# qtpy_midibff.net
KiCad netlist of a schematic drawn in EAGLE
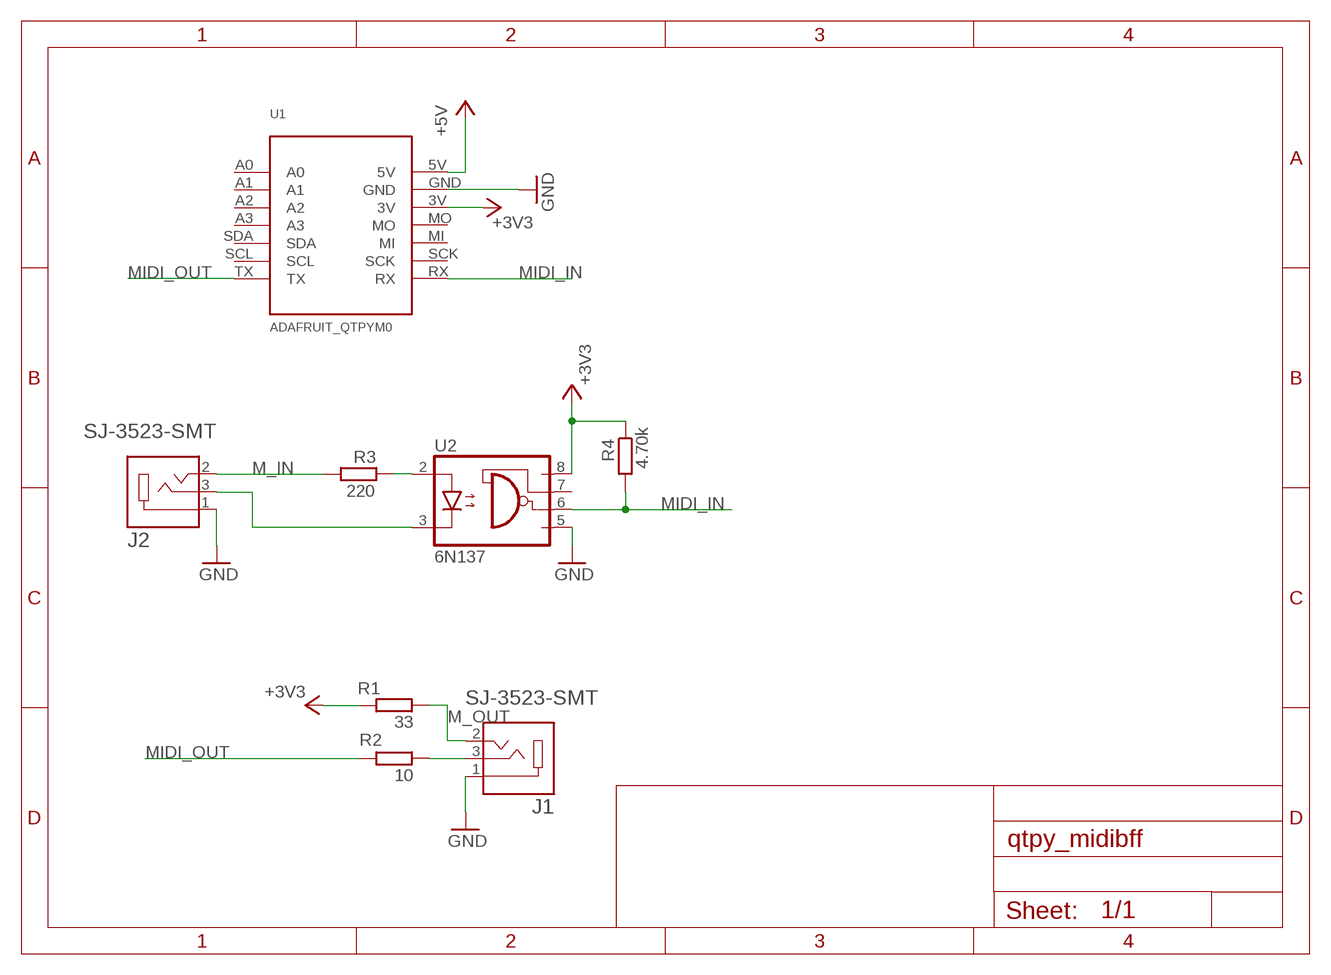
[diagram p0: schematic, sheet 1]

(export (version "E")
  (design (tool "Eeschema 10.0.6"))
  (components
    (comp (ref "J1")
      (value "SJ-3523-SMT")
      (footprint "eagle-import:CUI_SJ-3523-SMT")
      (fields
        (field (name "DIGI-KEY_PART_NUMBER") "CP-3523SJCT-ND")
        (field (name "MF") "CUI Devices")
        (field (name "MP") "SJ-3523-SMT-TR")
      )
      (libsource (lib "eagle-import") (part "SJ-3523-SMT"))
    )
    (comp (ref "J2")
      (value "SJ-3523-SMT")
      (footprint "eagle-import:CUI_SJ-3523-SMT")
      (fields
        (field (name "DIGI-KEY_PART_NUMBER") "CP-3523SJCT-ND")
        (field (name "MF") "CUI Devices")
        (field (name "MP") "SJ-3523-SMT-TR")
      )
      (libsource (lib "eagle-import") (part "SJ-3523-SMT"))
    )
    (comp (ref "R1")
      (value "33")
      (footprint "eagle-import:0204_7")
      (libsource (lib "eagle-import") (part "R-EU_0204/7"))
    )
    (comp (ref "R2")
      (value "10")
      (footprint "eagle-import:0204_7")
      (libsource (lib "eagle-import") (part "R-EU_0204/7"))
    )
    (comp (ref "R3")
      (value "220")
      (footprint "eagle-import:0204_7")
      (libsource (lib "eagle-import") (part "R-EU_0204/7"))
    )
    (comp (ref "R4")
      (value "4.70k")
      (footprint "eagle-import:0204_7")
      (libsource (lib "eagle-import") (part "R-EU_0204/7"))
    )
    (comp (ref "U1")
      (value "ADAFRUIT_QTPYM0")
      (footprint "eagle-import:ADAFRUIT_QTPY_M0")
      (libsource (lib "eagle-import") (part "ADAFRUIT_QTPYM0"))
    )
    (comp (ref "U2")
      (value "6N137")
      (footprint "eagle-import:DIL08")
      (libsource (lib "eagle-import") (part "6N137"))
    )
  )
  (nets
    (net (code "1") (name "+3V3") (class "Default")
      (node (ref "R1") (pin "2") (pinfunction "2_2") (pintype "passive"))
      (node (ref "R4") (pin "1") (pinfunction "1_1") (pintype "passive"))
      (node (ref "U1") (pin "3V") (pinfunction "3V_3V") (pintype "bidirectional"))
      (node (ref "U2") (pin "8") (pinfunction "VCC_8") (pintype "passive"))
    )
    (net (code "2") (name "+5V") (class "Default")
      (node (ref "U1") (pin "5V") (pinfunction "5V_5V") (pintype "bidirectional"))
    )
    (net (code "3") (name "/MIDI_IN") (class "Default")
      (node (ref "R4") (pin "2") (pinfunction "2_2") (pintype "passive"))
      (node (ref "U1") (pin "RX") (pinfunction "RX_RX") (pintype "bidirectional"))
      (node (ref "U2") (pin "6") (pinfunction "VO_6") (pintype "passive"))
    )
    (net (code "4") (name "/MIDI_OUT") (class "Default")
      (node (ref "R2") (pin "2") (pinfunction "2_2") (pintype "passive"))
      (node (ref "U1") (pin "TX") (pinfunction "TX_TX") (pintype "bidirectional"))
    )
    (net (code "5") (name "/M_IN") (class "Default")
      (node (ref "J2") (pin "2") (pinfunction "2_2") (pintype "passive"))
      (node (ref "R3") (pin "2") (pinfunction "2_2") (pintype "passive"))
    )
    (net (code "6") (name "/M_OUT") (class "Default")
      (node (ref "J1") (pin "2") (pinfunction "2_2") (pintype "passive"))
      (node (ref "R1") (pin "1") (pinfunction "1_1") (pintype "passive"))
    )
    (net (code "7") (name "GND") (class "Default")
      (node (ref "J1") (pin "1") (pinfunction "1_1") (pintype "passive"))
      (node (ref "J2") (pin "1") (pinfunction "1_1") (pintype "passive"))
      (node (ref "U1") (pin "GND") (pinfunction "GND_GND") (pintype "bidirectional"))
      (node (ref "U2") (pin "5") (pinfunction "GND_5") (pintype "passive"))
    )
    (net (code "8") (name "Net-(J1-Pad3)") (class "Default")
      (node (ref "J1") (pin "3") (pinfunction "3_3") (pintype "passive"))
      (node (ref "R2") (pin "1") (pinfunction "1_1") (pintype "passive"))
    )
    (net (code "9") (name "Net-(U2-A)") (class "Default")
      (node (ref "R3") (pin "1") (pinfunction "1_1") (pintype "passive"))
      (node (ref "U2") (pin "2") (pinfunction "A_2") (pintype "passive"))
    )
    (net (code "10") (name "Net-(U2-C)") (class "Default")
      (node (ref "J2") (pin "3") (pinfunction "3_3") (pintype "passive"))
      (node (ref "U2") (pin "3") (pinfunction "C_3") (pintype "passive"))
    )
    (net (code "11") (name "unconnected-(U1-PadA0)") (class "Default")
      (node (ref "U1") (pin "A0") (pinfunction "A0_A0") (pintype "bidirectional"))
    )
    (net (code "12") (name "unconnected-(U1-PadA1)") (class "Default")
      (node (ref "U1") (pin "A1") (pinfunction "A1_A1") (pintype "bidirectional"))
    )
    (net (code "13") (name "unconnected-(U1-PadA2)") (class "Default")
      (node (ref "U1") (pin "A2") (pinfunction "A2_A2") (pintype "bidirectional"))
    )
    (net (code "14") (name "unconnected-(U1-PadA3)") (class "Default")
      (node (ref "U1") (pin "A3") (pinfunction "A3_A3") (pintype "bidirectional"))
    )
    (net (code "15") (name "unconnected-(U1-PadMI)") (class "Default")
      (node (ref "U1") (pin "MI") (pinfunction "MI_MI") (pintype "bidirectional"))
    )
    (net (code "16") (name "unconnected-(U1-PadMO)") (class "Default")
      (node (ref "U1") (pin "MO") (pinfunction "MO_MO") (pintype "bidirectional"))
    )
    (net (code "17") (name "unconnected-(U1-PadSCK)") (class "Default")
      (node (ref "U1") (pin "SCK") (pinfunction "SCK_SCK") (pintype "bidirectional"))
    )
    (net (code "18") (name "unconnected-(U1-PadSCL)") (class "Default")
      (node (ref "U1") (pin "SCL") (pinfunction "SCL_SCL") (pintype "bidirectional"))
    )
    (net (code "19") (name "unconnected-(U1-PadSDA)") (class "Default")
      (node (ref "U1") (pin "SDA") (pinfunction "SDA_SDA") (pintype "bidirectional"))
    )
    (net (code "20") (name "unconnected-(U2-VE-Pad7)") (class "Default")
      (node (ref "U2") (pin "7") (pinfunction "VE_7") (pintype "passive"))
    )
  )
)
